# axiom_beta_interface_dummy_v0_13_r1_1_46.net
KiCad netlist of a schematic drawn in EAGLE
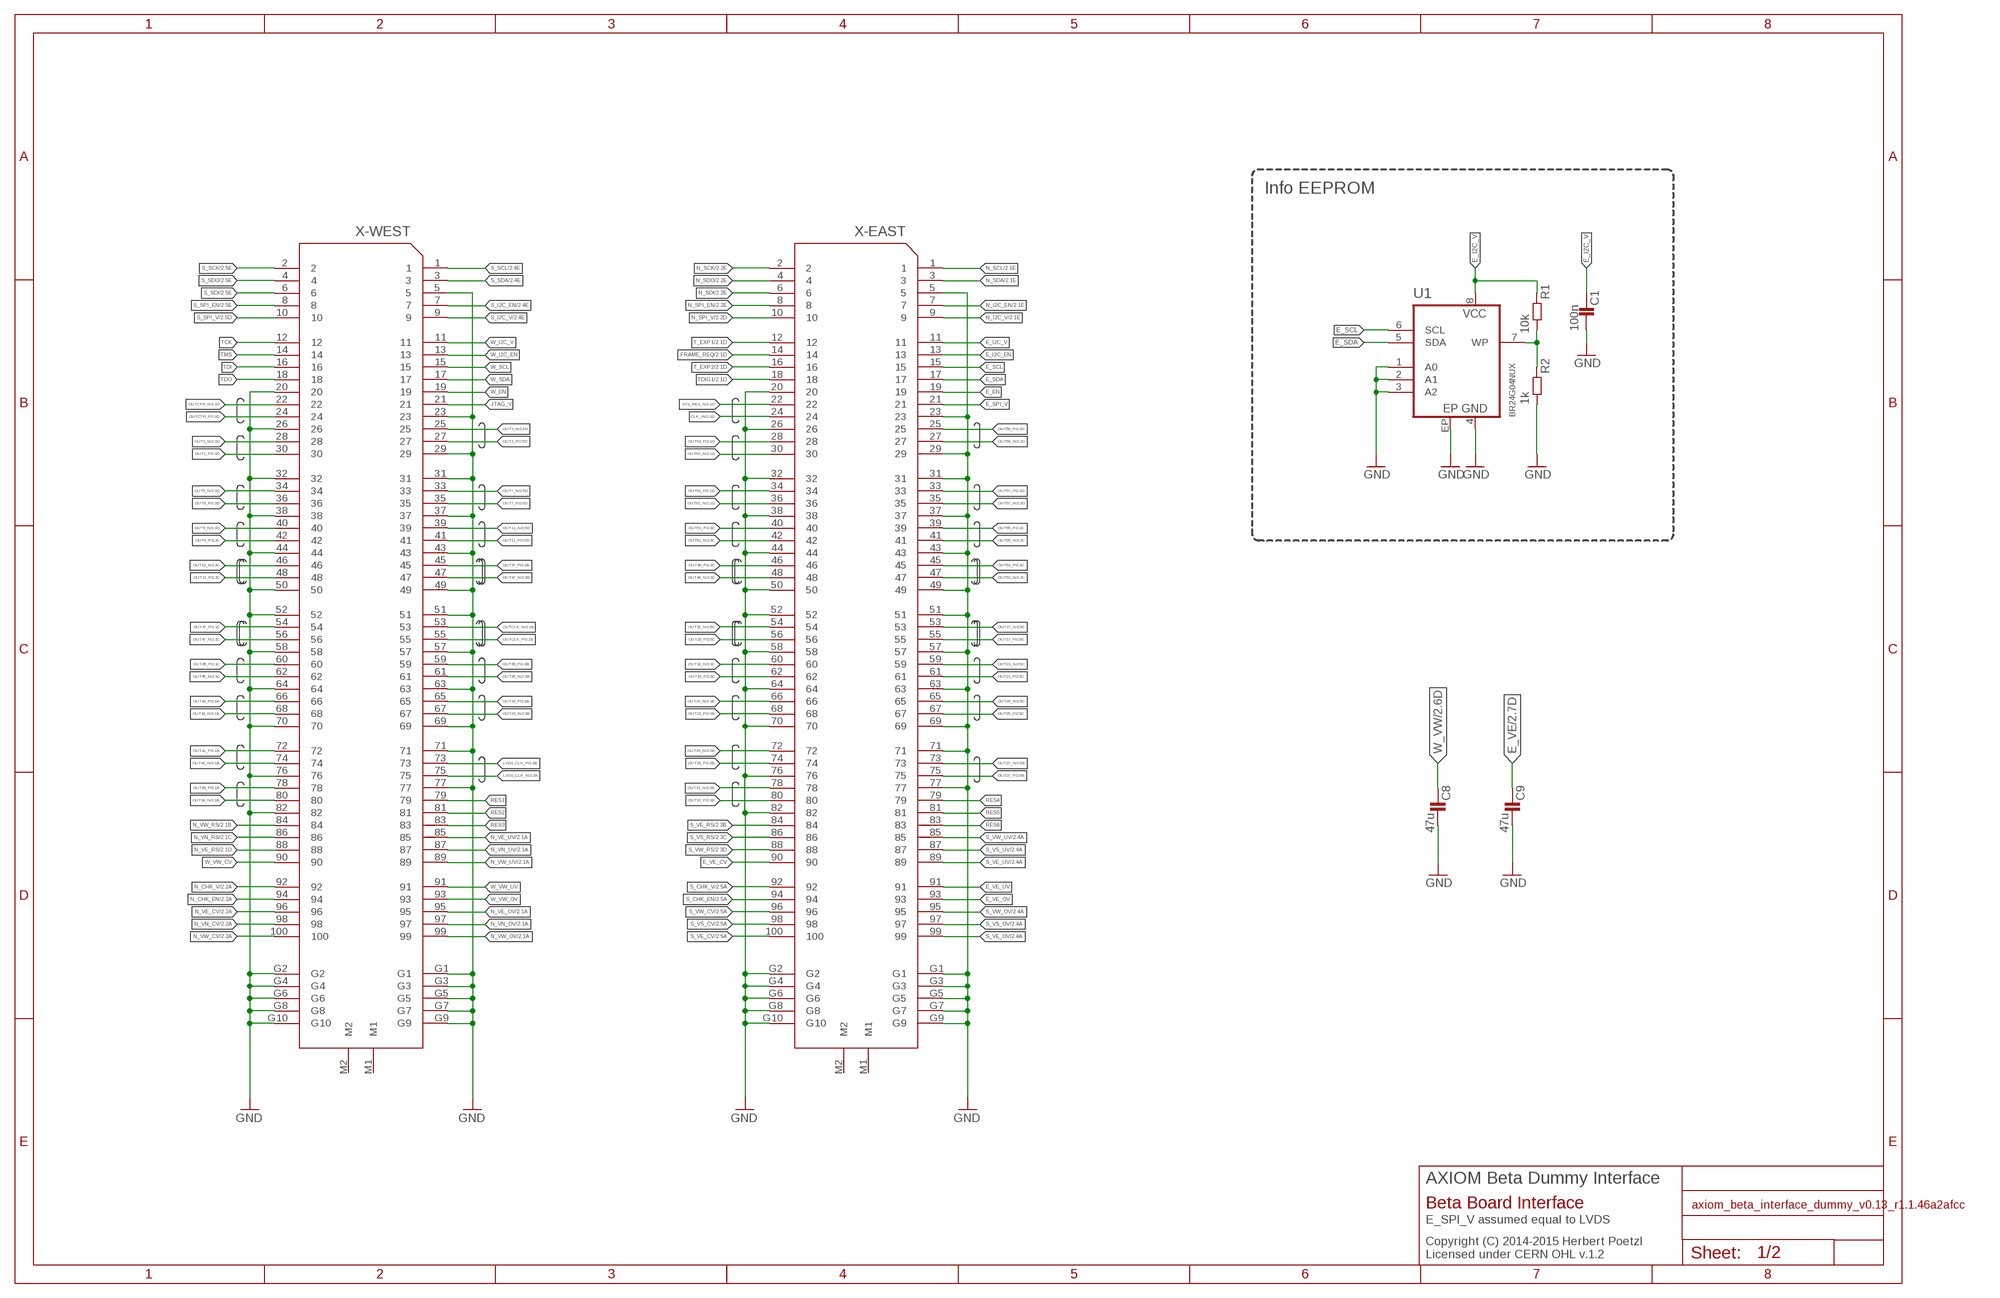
[diagram p0: schematic, sheet 1]
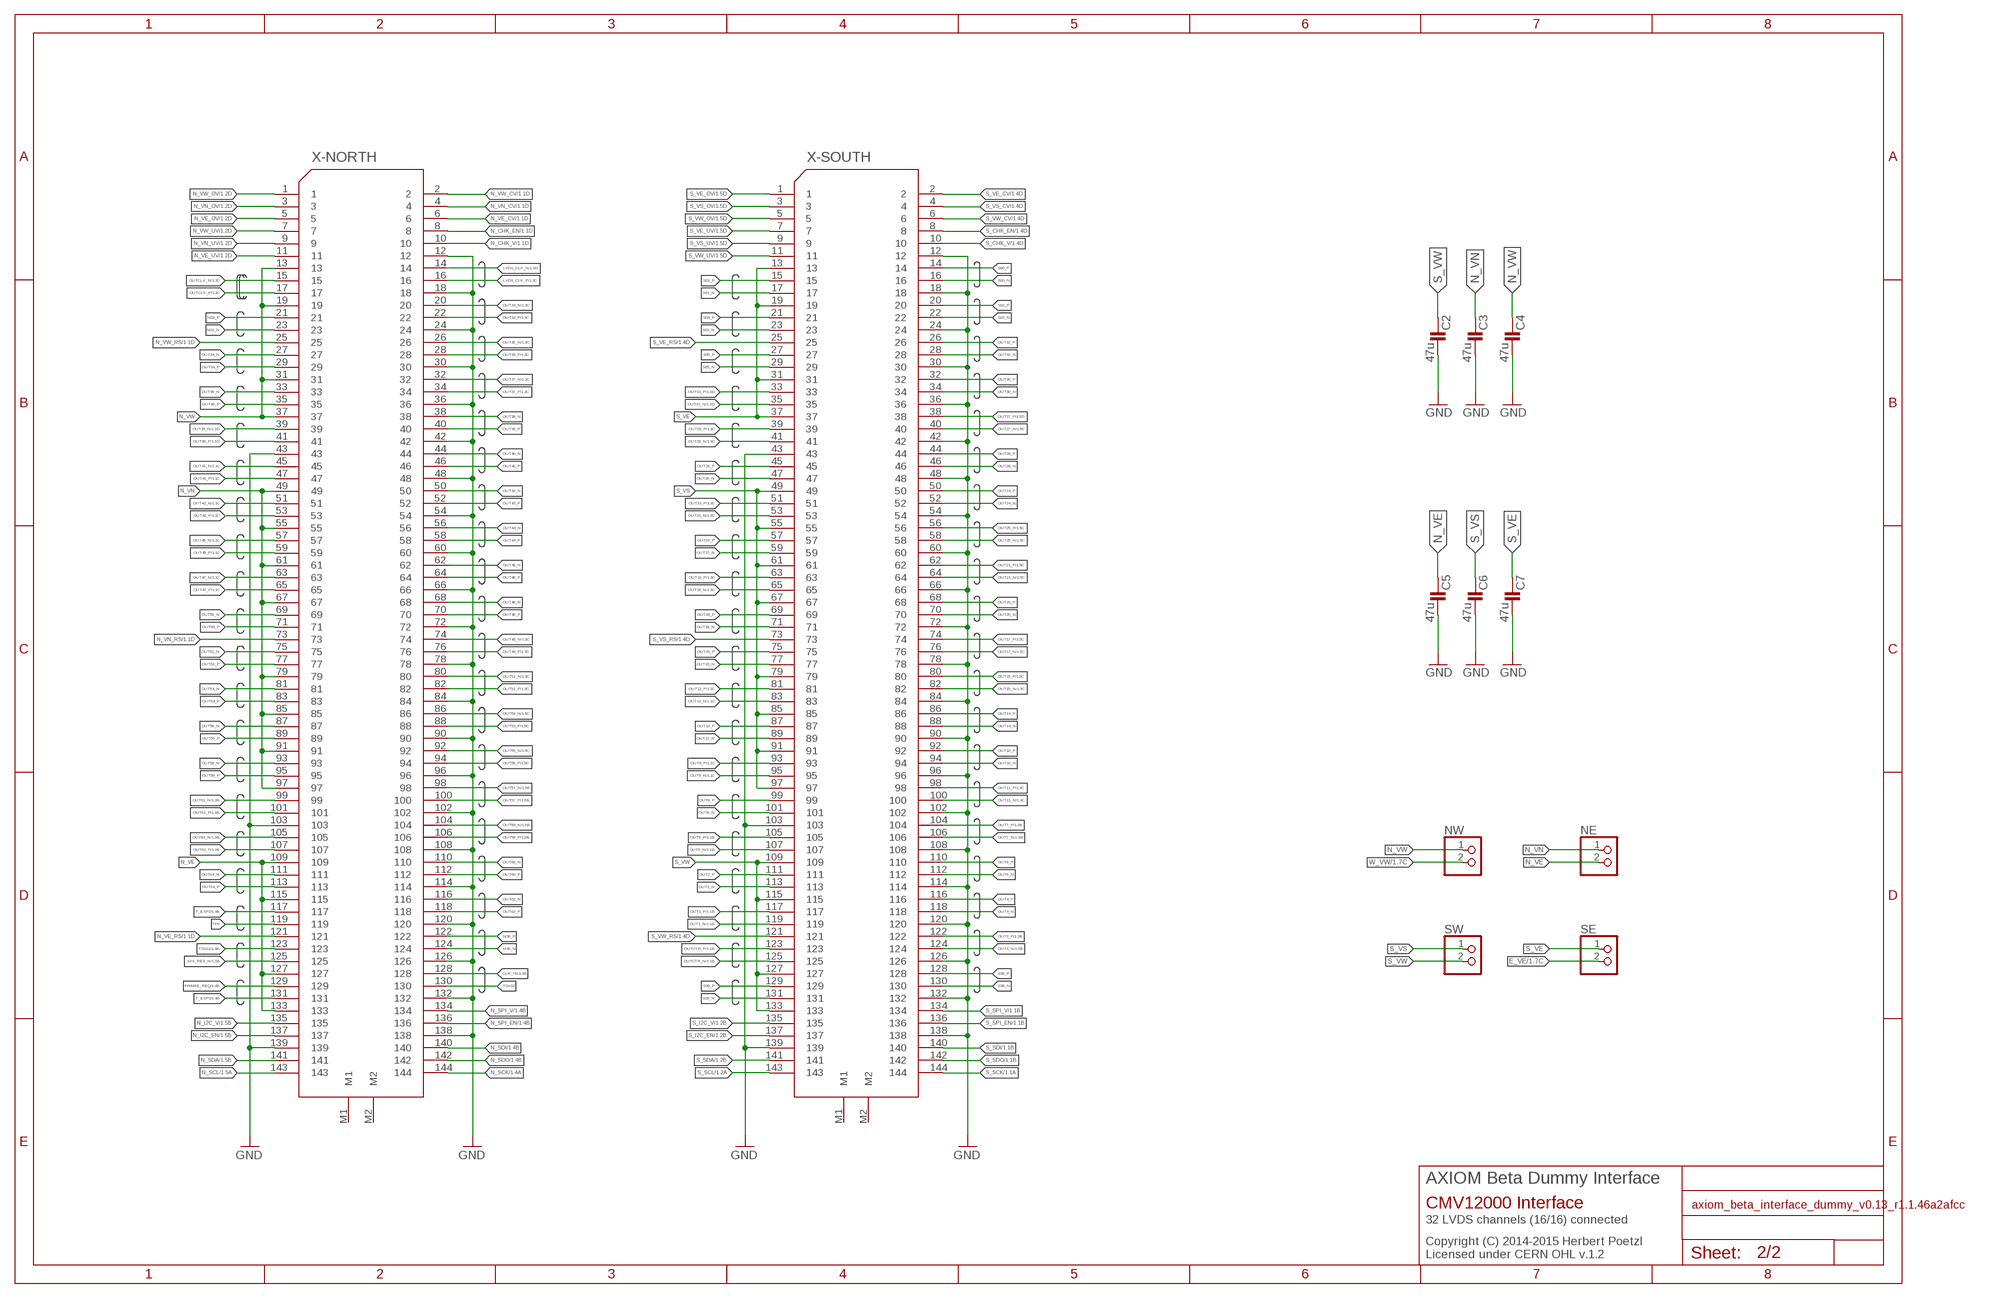
[diagram p1: schematic, sheet 2]

(export (version "E")
  (design (tool "Eeschema 10.0.6"))
  (components
    (comp (ref "C2")
      (value "47u")
      (footprint "eagle-import:0805-B")
      (libsource (lib "eagle-import") (part "C0805-B"))
    )
    (comp (ref "C3")
      (value "47u")
      (footprint "eagle-import:0805-B")
      (libsource (lib "eagle-import") (part "C0805-B"))
    )
    (comp (ref "C4")
      (value "47u")
      (footprint "eagle-import:0805-B")
      (libsource (lib "eagle-import") (part "C0805-B"))
    )
    (comp (ref "C5")
      (value "47u")
      (footprint "eagle-import:0805-B")
      (libsource (lib "eagle-import") (part "C0805-B"))
    )
    (comp (ref "C6")
      (value "47u")
      (footprint "eagle-import:0805-B")
      (libsource (lib "eagle-import") (part "C0805-B"))
    )
    (comp (ref "C7")
      (value "47u")
      (footprint "eagle-import:0805-B")
      (libsource (lib "eagle-import") (part "C0805-B"))
    )
    (comp (ref "NE")
      (value "PINHD-1X02_2.54")
      (footprint "eagle-import:1X02")
      (libsource (lib "eagle-import") (part "PINHD-1X02_2.54"))
    )
    (comp (ref "NW")
      (value "PINHD-1X02_2.54")
      (footprint "eagle-import:1X02")
      (libsource (lib "eagle-import") (part "PINHD-1X02_2.54"))
    )
    (comp (ref "SE")
      (value "PINHD-1X02_2.54")
      (footprint "eagle-import:1X02")
      (libsource (lib "eagle-import") (part "PINHD-1X02_2.54"))
    )
    (comp (ref "SW")
      (value "PINHD-1X02_2.54")
      (footprint "eagle-import:1X02")
      (libsource (lib "eagle-import") (part "PINHD-1X02_2.54"))
    )
    (comp (ref "X-NORTH")
      (value "FX10-144S")
      (footprint "eagle-import:FX10A-144S")
      (libsource (lib "eagle-import") (part "FX10-144S"))
    )
    (comp (ref "X-SOUTH")
      (value "FX10-144S")
      (footprint "eagle-import:FX10A-144S")
      (libsource (lib "eagle-import") (part "FX10-144S"))
    )
    (comp (ref "C1")
      (value "100n")
      (footprint "eagle-import:0402-B")
      (libsource (lib "eagle-import") (part "C0402-B"))
    )
    (comp (ref "C8")
      (value "47u")
      (footprint "eagle-import:0805-B")
      (libsource (lib "eagle-import") (part "C0805-B"))
    )
    (comp (ref "C9")
      (value "47u")
      (footprint "eagle-import:0805-B")
      (libsource (lib "eagle-import") (part "C0805-B"))
    )
    (comp (ref "R1")
      (value "10k")
      (footprint "eagle-import:0402-B")
      (libsource (lib "eagle-import") (part "R0402-B"))
    )
    (comp (ref "R2")
      (value "1k")
      (footprint "eagle-import:0402-B")
      (libsource (lib "eagle-import") (part "R0402-B"))
    )
    (comp (ref "U1")
      (value "BR24G04NUX")
      (footprint "eagle-import:DFN200X300X100-9N")
      (libsource (lib "eagle-import") (part "BR24G04NUX"))
    )
    (comp (ref "X-EAST")
      (value "FX10-100/10P")
      (footprint "eagle-import:FX10A-100P_10")
      (libsource (lib "eagle-import") (part "FX10-100/10P"))
    )
    (comp (ref "X-WEST")
      (value "FX10-100/10P")
      (footprint "eagle-import:FX10A-100P_10")
      (libsource (lib "eagle-import") (part "FX10-100/10P"))
    )
  )
  (nets
    (net (code "1") (name "CLK_IN") (class "Default")
      (node (ref "X-EAST") (pin "24") (pinfunction "24_24") (pintype "bidirectional"))
      (node (ref "X-NORTH") (pin "128") (pinfunction "128_128") (pintype "bidirectional"))
    )
    (net (code "2") (name "E_EN") (class "Default")
      (node (ref "X-EAST") (pin "19") (pinfunction "19_19") (pintype "bidirectional"))
    )
    (net (code "3") (name "E_I2C_EN") (class "Default")
      (node (ref "X-EAST") (pin "13") (pinfunction "13_13") (pintype "bidirectional"))
    )
    (net (code "4") (name "E_I2C_V") (class "Default")
      (node (ref "C1") (pin "1") (pinfunction "1_1") (pintype "passive"))
      (node (ref "R1") (pin "1") (pinfunction "1_1") (pintype "passive"))
      (node (ref "U1") (pin "8") (pinfunction "VCC_8") (pintype "power_in"))
      (node (ref "X-EAST") (pin "11") (pinfunction "11_11") (pintype "bidirectional"))
    )
    (net (code "5") (name "E_SCL") (class "Default")
      (node (ref "U1") (pin "6") (pinfunction "SCL_6") (pintype "input"))
      (node (ref "X-EAST") (pin "15") (pinfunction "15_15") (pintype "bidirectional"))
    )
    (net (code "6") (name "E_SDA") (class "Default")
      (node (ref "U1") (pin "5") (pinfunction "SDA_5") (pintype "bidirectional"))
      (node (ref "X-EAST") (pin "17") (pinfunction "17_17") (pintype "bidirectional"))
    )
    (net (code "7") (name "E_SPI_V") (class "Default")
      (node (ref "X-EAST") (pin "21") (pinfunction "21_21") (pintype "bidirectional"))
    )
    (net (code "8") (name "E_VE") (class "Default")
      (node (ref "C9") (pin "1") (pinfunction "1_1") (pintype "passive"))
      (node (ref "SE") (pin "2") (pinfunction "2_2") (pintype "passive"))
    )
    (net (code "9") (name "E_VE_CV") (class "Default")
      (node (ref "X-EAST") (pin "90") (pinfunction "90_90") (pintype "bidirectional"))
    )
    (net (code "10") (name "E_VE_OV") (class "Default")
      (node (ref "X-EAST") (pin "93") (pinfunction "93_93") (pintype "bidirectional"))
    )
    (net (code "11") (name "E_VE_UV") (class "Default")
      (node (ref "X-EAST") (pin "91") (pinfunction "91_91") (pintype "bidirectional"))
    )
    (net (code "12") (name "FRAME_REQ") (class "Default")
      (node (ref "X-EAST") (pin "14") (pinfunction "14_14") (pintype "bidirectional"))
      (node (ref "X-NORTH") (pin "129") (pinfunction "129_129") (pintype "bidirectional"))
    )
    (net (code "13") (name "GND") (class "Default")
      (node (ref "C1") (pin "2") (pinfunction "2_2") (pintype "passive"))
      (node (ref "C2") (pin "2") (pinfunction "2_2") (pintype "passive"))
      (node (ref "C3") (pin "2") (pinfunction "2_2") (pintype "passive"))
      (node (ref "C4") (pin "2") (pinfunction "2_2") (pintype "passive"))
      (node (ref "C5") (pin "2") (pinfunction "2_2") (pintype "passive"))
      (node (ref "C6") (pin "2") (pinfunction "2_2") (pintype "passive"))
      (node (ref "C7") (pin "2") (pinfunction "2_2") (pintype "passive"))
      (node (ref "C8") (pin "2") (pinfunction "2_2") (pintype "passive"))
      (node (ref "C9") (pin "2") (pinfunction "2_2") (pintype "passive"))
      (node (ref "R2") (pin "2") (pinfunction "2_2") (pintype "passive"))
      (node (ref "U1") (pin "1") (pinfunction "A0_1") (pintype "input"))
      (node (ref "U1") (pin "2") (pinfunction "A1_2") (pintype "input"))
      (node (ref "U1") (pin "3") (pinfunction "A2_3") (pintype "input"))
      (node (ref "U1") (pin "4") (pinfunction "GND_4") (pintype "passive"))
      (node (ref "U1") (pin "EP") (pinfunction "EP_EP") (pintype "passive"))
      (node (ref "X-EAST") (pin "20") (pinfunction "20_20") (pintype "bidirectional"))
      (node (ref "X-EAST") (pin "23") (pinfunction "23_23") (pintype "bidirectional"))
      (node (ref "X-EAST") (pin "26") (pinfunction "26_26") (pintype "bidirectional"))
      (node (ref "X-EAST") (pin "29") (pinfunction "29_29") (pintype "bidirectional"))
      (node (ref "X-EAST") (pin "31") (pinfunction "31_31") (pintype "bidirectional"))
      (node (ref "X-EAST") (pin "32") (pinfunction "32_32") (pintype "bidirectional"))
      (node (ref "X-EAST") (pin "37") (pinfunction "37_37") (pintype "bidirectional"))
      (node (ref "X-EAST") (pin "38") (pinfunction "38_38") (pintype "bidirectional"))
      (node (ref "X-EAST") (pin "43") (pinfunction "43_43") (pintype "bidirectional"))
      (node (ref "X-EAST") (pin "44") (pinfunction "44_44") (pintype "bidirectional"))
      (node (ref "X-EAST") (pin "49") (pinfunction "49_49") (pintype "bidirectional"))
      (node (ref "X-EAST") (pin "5") (pinfunction "5_5") (pintype "bidirectional"))
      (node (ref "X-EAST") (pin "50") (pinfunction "50_50") (pintype "bidirectional"))
      (node (ref "X-EAST") (pin "51") (pinfunction "51_51") (pintype "bidirectional"))
      (node (ref "X-EAST") (pin "52") (pinfunction "52_52") (pintype "bidirectional"))
      (node (ref "X-EAST") (pin "57") (pinfunction "57_57") (pintype "bidirectional"))
      (node (ref "X-EAST") (pin "58") (pinfunction "58_58") (pintype "bidirectional"))
      (node (ref "X-EAST") (pin "63") (pinfunction "63_63") (pintype "bidirectional"))
      (node (ref "X-EAST") (pin "64") (pinfunction "64_64") (pintype "bidirectional"))
      (node (ref "X-EAST") (pin "69") (pinfunction "69_69") (pintype "bidirectional"))
      (node (ref "X-EAST") (pin "70") (pinfunction "70_70") (pintype "bidirectional"))
      (node (ref "X-EAST") (pin "71") (pinfunction "71_71") (pintype "bidirectional"))
      (node (ref "X-EAST") (pin "76") (pinfunction "76_76") (pintype "bidirectional"))
      (node (ref "X-EAST") (pin "77") (pinfunction "77_77") (pintype "bidirectional"))
      (node (ref "X-EAST") (pin "82") (pinfunction "82_82") (pintype "bidirectional"))
      (node (ref "X-EAST") (pin "G1") (pinfunction "G1_G1") (pintype "bidirectional"))
      (node (ref "X-EAST") (pin "G10") (pinfunction "G10_G10") (pintype "bidirectional"))
      (node (ref "X-EAST") (pin "G2") (pinfunction "G2_G2") (pintype "bidirectional"))
      (node (ref "X-EAST") (pin "G3") (pinfunction "G3_G3") (pintype "bidirectional"))
      (node (ref "X-EAST") (pin "G4") (pinfunction "G4_G4") (pintype "bidirectional"))
      (node (ref "X-EAST") (pin "G5") (pinfunction "G5_G5") (pintype "bidirectional"))
      (node (ref "X-EAST") (pin "G6") (pinfunction "G6_G6") (pintype "bidirectional"))
      (node (ref "X-EAST") (pin "G7") (pinfunction "G7_G7") (pintype "bidirectional"))
      (node (ref "X-EAST") (pin "G8") (pinfunction "G8_G8") (pintype "bidirectional"))
      (node (ref "X-EAST") (pin "G9") (pinfunction "G9_G9") (pintype "bidirectional"))
      (node (ref "X-NORTH") (pin "102") (pinfunction "102_102") (pintype "bidirectional"))
      (node (ref "X-NORTH") (pin "103") (pinfunction "103_103") (pintype "bidirectional"))
      (node (ref "X-NORTH") (pin "108") (pinfunction "108_108") (pintype "bidirectional"))
      (node (ref "X-NORTH") (pin "114") (pinfunction "114_114") (pintype "bidirectional"))
      (node (ref "X-NORTH") (pin "12") (pinfunction "12_12") (pintype "bidirectional"))
      (node (ref "X-NORTH") (pin "120") (pinfunction "120_120") (pintype "bidirectional"))
      (node (ref "X-NORTH") (pin "126") (pinfunction "126_126") (pintype "bidirectional"))
      (node (ref "X-NORTH") (pin "132") (pinfunction "132_132") (pintype "bidirectional"))
      (node (ref "X-NORTH") (pin "138") (pinfunction "138_138") (pintype "bidirectional"))
      (node (ref "X-NORTH") (pin "139") (pinfunction "139_139") (pintype "bidirectional"))
      (node (ref "X-NORTH") (pin "18") (pinfunction "18_18") (pintype "bidirectional"))
      (node (ref "X-NORTH") (pin "24") (pinfunction "24_24") (pintype "bidirectional"))
      (node (ref "X-NORTH") (pin "30") (pinfunction "30_30") (pintype "bidirectional"))
      (node (ref "X-NORTH") (pin "36") (pinfunction "36_36") (pintype "bidirectional"))
      (node (ref "X-NORTH") (pin "42") (pinfunction "42_42") (pintype "bidirectional"))
      (node (ref "X-NORTH") (pin "43") (pinfunction "43_43") (pintype "bidirectional"))
      (node (ref "X-NORTH") (pin "48") (pinfunction "48_48") (pintype "bidirectional"))
      (node (ref "X-NORTH") (pin "54") (pinfunction "54_54") (pintype "bidirectional"))
      (node (ref "X-NORTH") (pin "60") (pinfunction "60_60") (pintype "bidirectional"))
      (node (ref "X-NORTH") (pin "66") (pinfunction "66_66") (pintype "bidirectional"))
      (node (ref "X-NORTH") (pin "72") (pinfunction "72_72") (pintype "bidirectional"))
      (node (ref "X-NORTH") (pin "78") (pinfunction "78_78") (pintype "bidirectional"))
      (node (ref "X-NORTH") (pin "84") (pinfunction "84_84") (pintype "bidirectional"))
      (node (ref "X-NORTH") (pin "90") (pinfunction "90_90") (pintype "bidirectional"))
      (node (ref "X-NORTH") (pin "96") (pinfunction "96_96") (pintype "bidirectional"))
      (node (ref "X-SOUTH") (pin "102") (pinfunction "102_102") (pintype "bidirectional"))
      (node (ref "X-SOUTH") (pin "103") (pinfunction "103_103") (pintype "bidirectional"))
      (node (ref "X-SOUTH") (pin "108") (pinfunction "108_108") (pintype "bidirectional"))
      (node (ref "X-SOUTH") (pin "114") (pinfunction "114_114") (pintype "bidirectional"))
      (node (ref "X-SOUTH") (pin "12") (pinfunction "12_12") (pintype "bidirectional"))
      (node (ref "X-SOUTH") (pin "120") (pinfunction "120_120") (pintype "bidirectional"))
      (node (ref "X-SOUTH") (pin "126") (pinfunction "126_126") (pintype "bidirectional"))
      (node (ref "X-SOUTH") (pin "132") (pinfunction "132_132") (pintype "bidirectional"))
      (node (ref "X-SOUTH") (pin "138") (pinfunction "138_138") (pintype "bidirectional"))
      (node (ref "X-SOUTH") (pin "139") (pinfunction "139_139") (pintype "bidirectional"))
      (node (ref "X-SOUTH") (pin "18") (pinfunction "18_18") (pintype "bidirectional"))
      (node (ref "X-SOUTH") (pin "24") (pinfunction "24_24") (pintype "bidirectional"))
      (node (ref "X-SOUTH") (pin "30") (pinfunction "30_30") (pintype "bidirectional"))
      (node (ref "X-SOUTH") (pin "36") (pinfunction "36_36") (pintype "bidirectional"))
      (node (ref "X-SOUTH") (pin "42") (pinfunction "42_42") (pintype "bidirectional"))
      (node (ref "X-SOUTH") (pin "43") (pinfunction "43_43") (pintype "bidirectional"))
      (node (ref "X-SOUTH") (pin "48") (pinfunction "48_48") (pintype "bidirectional"))
      (node (ref "X-SOUTH") (pin "54") (pinfunction "54_54") (pintype "bidirectional"))
      (node (ref "X-SOUTH") (pin "60") (pinfunction "60_60") (pintype "bidirectional"))
      (node (ref "X-SOUTH") (pin "66") (pinfunction "66_66") (pintype "bidirectional"))
      (node (ref "X-SOUTH") (pin "72") (pinfunction "72_72") (pintype "bidirectional"))
      (node (ref "X-SOUTH") (pin "78") (pinfunction "78_78") (pintype "bidirectional"))
      (node (ref "X-SOUTH") (pin "84") (pinfunction "84_84") (pintype "bidirectional"))
      (node (ref "X-SOUTH") (pin "90") (pinfunction "90_90") (pintype "bidirectional"))
      (node (ref "X-SOUTH") (pin "96") (pinfunction "96_96") (pintype "bidirectional"))
      (node (ref "X-WEST") (pin "20") (pinfunction "20_20") (pintype "bidirectional"))
      (node (ref "X-WEST") (pin "23") (pinfunction "23_23") (pintype "bidirectional"))
      (node (ref "X-WEST") (pin "26") (pinfunction "26_26") (pintype "bidirectional"))
      (node (ref "X-WEST") (pin "29") (pinfunction "29_29") (pintype "bidirectional"))
      (node (ref "X-WEST") (pin "31") (pinfunction "31_31") (pintype "bidirectional"))
      (node (ref "X-WEST") (pin "32") (pinfunction "32_32") (pintype "bidirectional"))
      (node (ref "X-WEST") (pin "37") (pinfunction "37_37") (pintype "bidirectional"))
      (node (ref "X-WEST") (pin "38") (pinfunction "38_38") (pintype "bidirectional"))
      (node (ref "X-WEST") (pin "43") (pinfunction "43_43") (pintype "bidirectional"))
      (node (ref "X-WEST") (pin "44") (pinfunction "44_44") (pintype "bidirectional"))
      (node (ref "X-WEST") (pin "49") (pinfunction "49_49") (pintype "bidirectional"))
      (node (ref "X-WEST") (pin "5") (pinfunction "5_5") (pintype "bidirectional"))
      (node (ref "X-WEST") (pin "50") (pinfunction "50_50") (pintype "bidirectional"))
      (node (ref "X-WEST") (pin "51") (pinfunction "51_51") (pintype "bidirectional"))
      (node (ref "X-WEST") (pin "52") (pinfunction "52_52") (pintype "bidirectional"))
      (node (ref "X-WEST") (pin "57") (pinfunction "57_57") (pintype "bidirectional"))
      (node (ref "X-WEST") (pin "58") (pinfunction "58_58") (pintype "bidirectional"))
      (node (ref "X-WEST") (pin "63") (pinfunction "63_63") (pintype "bidirectional"))
      (node (ref "X-WEST") (pin "64") (pinfunction "64_64") (pintype "bidirectional"))
      (node (ref "X-WEST") (pin "69") (pinfunction "69_69") (pintype "bidirectional"))
      (node (ref "X-WEST") (pin "70") (pinfunction "70_70") (pintype "bidirectional"))
      (node (ref "X-WEST") (pin "71") (pinfunction "71_71") (pintype "bidirectional"))
      (node (ref "X-WEST") (pin "76") (pinfunction "76_76") (pintype "bidirectional"))
      (node (ref "X-WEST") (pin "77") (pinfunction "77_77") (pintype "bidirectional"))
      (node (ref "X-WEST") (pin "82") (pinfunction "82_82") (pintype "bidirectional"))
      (node (ref "X-WEST") (pin "G1") (pinfunction "G1_G1") (pintype "bidirectional"))
      (node (ref "X-WEST") (pin "G10") (pinfunction "G10_G10") (pintype "bidirectional"))
      (node (ref "X-WEST") (pin "G2") (pinfunction "G2_G2") (pintype "bidirectional"))
      (node (ref "X-WEST") (pin "G3") (pinfunction "G3_G3") (pintype "bidirectional"))
      (node (ref "X-WEST") (pin "G4") (pinfunction "G4_G4") (pintype "bidirectional"))
      (node (ref "X-WEST") (pin "G5") (pinfunction "G5_G5") (pintype "bidirectional"))
      (node (ref "X-WEST") (pin "G6") (pinfunction "G6_G6") (pintype "bidirectional"))
      (node (ref "X-WEST") (pin "G7") (pinfunction "G7_G7") (pintype "bidirectional"))
      (node (ref "X-WEST") (pin "G8") (pinfunction "G8_G8") (pintype "bidirectional"))
      (node (ref "X-WEST") (pin "G9") (pinfunction "G9_G9") (pintype "bidirectional"))
    )
    (net (code "14") (name "JTAG_V") (class "Default")
      (node (ref "X-WEST") (pin "21") (pinfunction "21_21") (pintype "bidirectional"))
    )
    (net (code "15") (name "LVDS_CLK_N") (class "Default")
      (node (ref "X-NORTH") (pin "14") (pinfunction "14_14") (pintype "bidirectional"))
      (node (ref "X-WEST") (pin "75") (pinfunction "75_75") (pintype "bidirectional"))
    )
    (net (code "16") (name "LVDS_CLK_P") (class "Default")
      (node (ref "X-NORTH") (pin "16") (pinfunction "16_16") (pintype "bidirectional"))
      (node (ref "X-WEST") (pin "73") (pinfunction "73_73") (pintype "bidirectional"))
    )
    (net (code "17") (name "N03_N") (class "Default")
      (node (ref "X-NORTH") (pin "23") (pinfunction "23_23") (pintype "bidirectional"))
    )
    (net (code "18") (name "N03_P") (class "Default")
      (node (ref "X-NORTH") (pin "21") (pinfunction "21_21") (pintype "bidirectional"))
    )
    (net (code "19") (name "N36_N") (class "Default")
      (node (ref "X-NORTH") (pin "124") (pinfunction "124_124") (pintype "bidirectional"))
    )
    (net (code "20") (name "N36_P") (class "Default")
      (node (ref "X-NORTH") (pin "122") (pinfunction "122_122") (pintype "bidirectional"))
    )
    (net (code "21") (name "N_CHK_EN") (class "Default")
      (node (ref "X-NORTH") (pin "8") (pinfunction "8_8") (pintype "bidirectional"))
      (node (ref "X-WEST") (pin "94") (pinfunction "94_94") (pintype "bidirectional"))
    )
    (net (code "22") (name "N_CHK_V") (class "Default")
      (node (ref "X-NORTH") (pin "10") (pinfunction "10_10") (pintype "bidirectional"))
      (node (ref "X-WEST") (pin "92") (pinfunction "92_92") (pintype "bidirectional"))
    )
    (net (code "23") (name "N_I2C_EN") (class "Default")
      (node (ref "X-EAST") (pin "7") (pinfunction "7_7") (pintype "bidirectional"))
      (node (ref "X-NORTH") (pin "137") (pinfunction "137_137") (pintype "bidirectional"))
    )
    (net (code "24") (name "N_I2C_V") (class "Default")
      (node (ref "X-EAST") (pin "9") (pinfunction "9_9") (pintype "bidirectional"))
      (node (ref "X-NORTH") (pin "135") (pinfunction "135_135") (pintype "bidirectional"))
    )
    (net (code "25") (name "N_SCK") (class "Default")
      (node (ref "X-EAST") (pin "2") (pinfunction "2_2") (pintype "bidirectional"))
      (node (ref "X-NORTH") (pin "144") (pinfunction "144_144") (pintype "bidirectional"))
    )
    (net (code "26") (name "N_SCL") (class "Default")
      (node (ref "X-EAST") (pin "1") (pinfunction "1_1") (pintype "bidirectional"))
      (node (ref "X-NORTH") (pin "143") (pinfunction "143_143") (pintype "bidirectional"))
    )
    (net (code "27") (name "N_SDA") (class "Default")
      (node (ref "X-EAST") (pin "3") (pinfunction "3_3") (pintype "bidirectional"))
      (node (ref "X-NORTH") (pin "141") (pinfunction "141_141") (pintype "bidirectional"))
    )
    (net (code "28") (name "N_SDI") (class "Default")
      (node (ref "X-EAST") (pin "6") (pinfunction "6_6") (pintype "bidirectional"))
      (node (ref "X-NORTH") (pin "140") (pinfunction "140_140") (pintype "bidirectional"))
    )
    (net (code "29") (name "N_SDO") (class "Default")
      (node (ref "X-EAST") (pin "4") (pinfunction "4_4") (pintype "bidirectional"))
      (node (ref "X-NORTH") (pin "142") (pinfunction "142_142") (pintype "bidirectional"))
    )
    (net (code "30") (name "N_SPI_EN") (class "Default")
      (node (ref "X-EAST") (pin "8") (pinfunction "8_8") (pintype "bidirectional"))
      (node (ref "X-NORTH") (pin "136") (pinfunction "136_136") (pintype "bidirectional"))
    )
    (net (code "31") (name "N_SPI_V") (class "Default")
      (node (ref "X-EAST") (pin "10") (pinfunction "10_10") (pintype "bidirectional"))
      (node (ref "X-NORTH") (pin "134") (pinfunction "134_134") (pintype "bidirectional"))
    )
    (net (code "32") (name "N_VE") (class "Default")
      (node (ref "C5") (pin "1") (pinfunction "1_1") (pintype "passive"))
      (node (ref "NE") (pin "2") (pinfunction "2_2") (pintype "passive"))
      (node (ref "X-NORTH") (pin "109") (pinfunction "109_109") (pintype "bidirectional"))
      (node (ref "X-NORTH") (pin "115") (pinfunction "115_115") (pintype "bidirectional"))
      (node (ref "X-NORTH") (pin "127") (pinfunction "127_127") (pintype "bidirectional"))
      (node (ref "X-NORTH") (pin "133") (pinfunction "133_133") (pintype "bidirectional"))
    )
    (net (code "33") (name "N_VE_CV") (class "Default")
      (node (ref "X-NORTH") (pin "6") (pinfunction "6_6") (pintype "bidirectional"))
      (node (ref "X-WEST") (pin "96") (pinfunction "96_96") (pintype "bidirectional"))
    )
    (net (code "34") (name "N_VE_OV") (class "Default")
      (node (ref "X-NORTH") (pin "5") (pinfunction "5_5") (pintype "bidirectional"))
      (node (ref "X-WEST") (pin "95") (pinfunction "95_95") (pintype "bidirectional"))
    )
    (net (code "35") (name "N_VE_RS") (class "Default")
      (node (ref "X-NORTH") (pin "121") (pinfunction "121_121") (pintype "bidirectional"))
      (node (ref "X-WEST") (pin "88") (pinfunction "88_88") (pintype "bidirectional"))
    )
    (net (code "36") (name "N_VE_UV") (class "Default")
      (node (ref "X-NORTH") (pin "11") (pinfunction "11_11") (pintype "bidirectional"))
      (node (ref "X-WEST") (pin "85") (pinfunction "85_85") (pintype "bidirectional"))
    )
    (net (code "37") (name "N_VN") (class "Default")
      (node (ref "C3") (pin "1") (pinfunction "1_1") (pintype "passive"))
      (node (ref "NE") (pin "1") (pinfunction "1_1") (pintype "passive"))
      (node (ref "X-NORTH") (pin "49") (pinfunction "49_49") (pintype "bidirectional"))
      (node (ref "X-NORTH") (pin "55") (pinfunction "55_55") (pintype "bidirectional"))
      (node (ref "X-NORTH") (pin "61") (pinfunction "61_61") (pintype "bidirectional"))
      (node (ref "X-NORTH") (pin "67") (pinfunction "67_67") (pintype "bidirectional"))
      (node (ref "X-NORTH") (pin "79") (pinfunction "79_79") (pintype "bidirectional"))
      (node (ref "X-NORTH") (pin "85") (pinfunction "85_85") (pintype "bidirectional"))
      (node (ref "X-NORTH") (pin "91") (pinfunction "91_91") (pintype "bidirectional"))
      (node (ref "X-NORTH") (pin "97") (pinfunction "97_97") (pintype "bidirectional"))
    )
    (net (code "38") (name "N_VN_CV") (class "Default")
      (node (ref "X-NORTH") (pin "4") (pinfunction "4_4") (pintype "bidirectional"))
      (node (ref "X-WEST") (pin "98") (pinfunction "98_98") (pintype "bidirectional"))
    )
    (net (code "39") (name "N_VN_OV") (class "Default")
      (node (ref "X-NORTH") (pin "3") (pinfunction "3_3") (pintype "bidirectional"))
      (node (ref "X-WEST") (pin "97") (pinfunction "97_97") (pintype "bidirectional"))
    )
    (net (code "40") (name "N_VN_RS") (class "Default")
      (node (ref "X-NORTH") (pin "73") (pinfunction "73_73") (pintype "bidirectional"))
      (node (ref "X-WEST") (pin "86") (pinfunction "86_86") (pintype "bidirectional"))
    )
    (net (code "41") (name "N_VN_UV") (class "Default")
      (node (ref "X-NORTH") (pin "9") (pinfunction "9_9") (pintype "bidirectional"))
      (node (ref "X-WEST") (pin "87") (pinfunction "87_87") (pintype "bidirectional"))
    )
    (net (code "42") (name "N_VW") (class "Default")
      (node (ref "C4") (pin "1") (pinfunction "1_1") (pintype "passive"))
      (node (ref "NW") (pin "1") (pinfunction "1_1") (pintype "passive"))
      (node (ref "X-NORTH") (pin "13") (pinfunction "13_13") (pintype "bidirectional"))
      (node (ref "X-NORTH") (pin "19") (pinfunction "19_19") (pintype "bidirectional"))
      (node (ref "X-NORTH") (pin "31") (pinfunction "31_31") (pintype "bidirectional"))
      (node (ref "X-NORTH") (pin "37") (pinfunction "37_37") (pintype "bidirectional"))
    )
    (net (code "43") (name "N_VW_CV") (class "Default")
      (node (ref "X-NORTH") (pin "2") (pinfunction "2_2") (pintype "bidirectional"))
      (node (ref "X-WEST") (pin "100") (pinfunction "100_100") (pintype "bidirectional"))
    )
    (net (code "44") (name "N_VW_OV") (class "Default")
      (node (ref "X-NORTH") (pin "1") (pinfunction "1_1") (pintype "bidirectional"))
      (node (ref "X-WEST") (pin "99") (pinfunction "99_99") (pintype "bidirectional"))
    )
    (net (code "45") (name "N_VW_RS") (class "Default")
      (node (ref "X-NORTH") (pin "25") (pinfunction "25_25") (pintype "bidirectional"))
      (node (ref "X-WEST") (pin "84") (pinfunction "84_84") (pintype "bidirectional"))
    )
    (net (code "46") (name "N_VW_UV") (class "Default")
      (node (ref "X-NORTH") (pin "7") (pinfunction "7_7") (pintype "bidirectional"))
      (node (ref "X-WEST") (pin "89") (pinfunction "89_89") (pintype "bidirectional"))
    )
    (net (code "47") (name "Net-(U1-WP)") (class "Default")
      (node (ref "R1") (pin "2") (pinfunction "2_2") (pintype "passive"))
      (node (ref "R2") (pin "1") (pinfunction "1_1") (pintype "passive"))
      (node (ref "U1") (pin "7") (pinfunction "WP_7") (pintype "input"))
    )
    (net (code "48") (name "OUT1_N") (class "Default")
      (node (ref "X-SOUTH") (pin "119") (pinfunction "119_119") (pintype "bidirectional"))
      (node (ref "X-WEST") (pin "28") (pinfunction "28_28") (pintype "bidirectional"))
    )
    (net (code "49") (name "OUT1_P") (class "Default")
      (node (ref "X-SOUTH") (pin "117") (pinfunction "117_117") (pintype "bidirectional"))
      (node (ref "X-WEST") (pin "30") (pinfunction "30_30") (pintype "bidirectional"))
    )
    (net (code "50") (name "OUT2_N") (class "Default")
      (node (ref "X-SOUTH") (pin "113") (pinfunction "113_113") (pintype "bidirectional"))
    )
    (net (code "51") (name "OUT2_P") (class "Default")
      (node (ref "X-SOUTH") (pin "111") (pinfunction "111_111") (pintype "bidirectional"))
    )
    (net (code "52") (name "OUT3_N") (class "Default")
      (node (ref "X-SOUTH") (pin "124") (pinfunction "124_124") (pintype "bidirectional"))
      (node (ref "X-WEST") (pin "25") (pinfunction "25_25") (pintype "bidirectional"))
    )
    (net (code "53") (name "OUT3_P") (class "Default")
      (node (ref "X-SOUTH") (pin "122") (pinfunction "122_122") (pintype "bidirectional"))
      (node (ref "X-WEST") (pin "27") (pinfunction "27_27") (pintype "bidirectional"))
    )
    (net (code "54") (name "OUT4_N") (class "Default")
      (node (ref "X-SOUTH") (pin "118") (pinfunction "118_118") (pintype "bidirectional"))
    )
    (net (code "55") (name "OUT4_P") (class "Default")
      (node (ref "X-SOUTH") (pin "116") (pinfunction "116_116") (pintype "bidirectional"))
    )
    (net (code "56") (name "OUT5_N") (class "Default")
      (node (ref "X-SOUTH") (pin "107") (pinfunction "107_107") (pintype "bidirectional"))
      (node (ref "X-WEST") (pin "34") (pinfunction "34_34") (pintype "bidirectional"))
    )
    (net (code "57") (name "OUT5_P") (class "Default")
      (node (ref "X-SOUTH") (pin "105") (pinfunction "105_105") (pintype "bidirectional"))
      (node (ref "X-WEST") (pin "36") (pinfunction "36_36") (pintype "bidirectional"))
    )
    (net (code "58") (name "OUT6_N") (class "Default")
      (node (ref "X-SOUTH") (pin "112") (pinfunction "112_112") (pintype "bidirectional"))
    )
    (net (code "59") (name "OUT6_P") (class "Default")
      (node (ref "X-SOUTH") (pin "110") (pinfunction "110_110") (pintype "bidirectional"))
    )
    (net (code "60") (name "OUT7_N") (class "Default")
      (node (ref "X-SOUTH") (pin "106") (pinfunction "106_106") (pintype "bidirectional"))
      (node (ref "X-WEST") (pin "33") (pinfunction "33_33") (pintype "bidirectional"))
    )
    (net (code "61") (name "OUT7_P") (class "Default")
      (node (ref "X-SOUTH") (pin "104") (pinfunction "104_104") (pintype "bidirectional"))
      (node (ref "X-WEST") (pin "35") (pinfunction "35_35") (pintype "bidirectional"))
    )
    (net (code "62") (name "OUT8_N") (class "Default")
      (node (ref "X-SOUTH") (pin "101") (pinfunction "101_101") (pintype "bidirectional"))
    )
    (net (code "63") (name "OUT8_P") (class "Default")
      (node (ref "X-SOUTH") (pin "99") (pinfunction "99_99") (pintype "bidirectional"))
    )
    (net (code "64") (name "OUT9_N") (class "Default")
      (node (ref "X-SOUTH") (pin "95") (pinfunction "95_95") (pintype "bidirectional"))
      (node (ref "X-WEST") (pin "40") (pinfunction "40_40") (pintype "bidirectional"))
    )
    (net (code "65") (name "OUT9_P") (class "Default")
      (node (ref "X-SOUTH") (pin "93") (pinfunction "93_93") (pintype "bidirectional"))
      (node (ref "X-WEST") (pin "42") (pinfunction "42_42") (pintype "bidirectional"))
    )
    (net (code "66") (name "OUT10_N") (class "Default")
      (node (ref "X-SOUTH") (pin "94") (pinfunction "94_94") (pintype "bidirectional"))
    )
    (net (code "67") (name "OUT10_P") (class "Default")
      (node (ref "X-SOUTH") (pin "92") (pinfunction "92_92") (pintype "bidirectional"))
    )
    (net (code "68") (name "OUT11_N") (class "Default")
      (node (ref "X-SOUTH") (pin "100") (pinfunction "100_100") (pintype "bidirectional"))
      (node (ref "X-WEST") (pin "39") (pinfunction "39_39") (pintype "bidirectional"))
    )
    (net (code "69") (name "OUT11_P") (class "Default")
      (node (ref "X-SOUTH") (pin "98") (pinfunction "98_98") (pintype "bidirectional"))
      (node (ref "X-WEST") (pin "41") (pinfunction "41_41") (pintype "bidirectional"))
    )
    (net (code "70") (name "OUT12_N") (class "Default")
      (node (ref "X-SOUTH") (pin "89") (pinfunction "89_89") (pintype "bidirectional"))
    )
    (net (code "71") (name "OUT12_P") (class "Default")
      (node (ref "X-SOUTH") (pin "87") (pinfunction "87_87") (pintype "bidirectional"))
    )
    (net (code "72") (name "OUT13_N") (class "Default")
      (node (ref "X-SOUTH") (pin "83") (pinfunction "83_83") (pintype "bidirectional"))
      (node (ref "X-WEST") (pin "46") (pinfunction "46_46") (pintype "bidirectional"))
    )
    (net (code "73") (name "OUT13_P") (class "Default")
      (node (ref "X-SOUTH") (pin "81") (pinfunction "81_81") (pintype "bidirectional"))
      (node (ref "X-WEST") (pin "48") (pinfunction "48_48") (pintype "bidirectional"))
    )
    (net (code "74") (name "OUT14_N") (class "Default")
      (node (ref "X-SOUTH") (pin "88") (pinfunction "88_88") (pintype "bidirectional"))
    )
    (net (code "75") (name "OUT14_P") (class "Default")
      (node (ref "X-SOUTH") (pin "86") (pinfunction "86_86") (pintype "bidirectional"))
    )
    (net (code "76") (name "OUT15_N") (class "Default")
      (node (ref "X-EAST") (pin "54") (pinfunction "54_54") (pintype "bidirectional"))
      (node (ref "X-SOUTH") (pin "82") (pinfunction "82_82") (pintype "bidirectional"))
    )
    (net (code "77") (name "OUT15_P") (class "Default")
      (node (ref "X-EAST") (pin "56") (pinfunction "56_56") (pintype "bidirectional"))
      (node (ref "X-SOUTH") (pin "80") (pinfunction "80_80") (pintype "bidirectional"))
    )
    (net (code "78") (name "OUT16_N") (class "Default")
      (node (ref "X-SOUTH") (pin "77") (pinfunction "77_77") (pintype "bidirectional"))
    )
    (net (code "79") (name "OUT16_P") (class "Default")
      (node (ref "X-SOUTH") (pin "75") (pinfunction "75_75") (pintype "bidirectional"))
    )
    (net (code "80") (name "OUT17_N") (class "Default")
      (node (ref "X-EAST") (pin "53") (pinfunction "53_53") (pintype "bidirectional"))
      (node (ref "X-SOUTH") (pin "76") (pinfunction "76_76") (pintype "bidirectional"))
    )
    (net (code "81") (name "OUT17_P") (class "Default")
      (node (ref "X-EAST") (pin "55") (pinfunction "55_55") (pintype "bidirectional"))
      (node (ref "X-SOUTH") (pin "74") (pinfunction "74_74") (pintype "bidirectional"))
    )
    (net (code "82") (name "OUT18_N") (class "Default")
      (node (ref "X-SOUTH") (pin "71") (pinfunction "71_71") (pintype "bidirectional"))
    )
    (net (code "83") (name "OUT18_P") (class "Default")
      (node (ref "X-SOUTH") (pin "69") (pinfunction "69_69") (pintype "bidirectional"))
    )
    (net (code "84") (name "OUT19_N") (class "Default")
      (node (ref "X-EAST") (pin "60") (pinfunction "60_60") (pintype "bidirectional"))
      (node (ref "X-SOUTH") (pin "65") (pinfunction "65_65") (pintype "bidirectional"))
    )
    (net (code "85") (name "OUT19_P") (class "Default")
      (node (ref "X-EAST") (pin "62") (pinfunction "62_62") (pintype "bidirectional"))
      (node (ref "X-SOUTH") (pin "63") (pinfunction "63_63") (pintype "bidirectional"))
    )
    (net (code "86") (name "OUT20_N") (class "Default")
      (node (ref "X-SOUTH") (pin "70") (pinfunction "70_70") (pintype "bidirectional"))
    )
    (net (code "87") (name "OUT20_P") (class "Default")
      (node (ref "X-SOUTH") (pin "68") (pinfunction "68_68") (pintype "bidirectional"))
    )
    (net (code "88") (name "OUT21_N") (class "Default")
      (node (ref "X-EAST") (pin "59") (pinfunction "59_59") (pintype "bidirectional"))
      (node (ref "X-SOUTH") (pin "64") (pinfunction "64_64") (pintype "bidirectional"))
    )
    (net (code "89") (name "OUT21_P") (class "Default")
      (node (ref "X-EAST") (pin "61") (pinfunction "61_61") (pintype "bidirectional"))
      (node (ref "X-SOUTH") (pin "62") (pinfunction "62_62") (pintype "bidirectional"))
    )
    (net (code "90") (name "OUT22_N") (class "Default")
      (node (ref "X-SOUTH") (pin "59") (pinfunction "59_59") (pintype "bidirectional"))
    )
    (net (code "91") (name "OUT22_P") (class "Default")
      (node (ref "X-SOUTH") (pin "57") (pinfunction "57_57") (pintype "bidirectional"))
    )
    (net (code "92") (name "OUT23_N") (class "Default")
      (node (ref "X-EAST") (pin "66") (pinfunction "66_66") (pintype "bidirectional"))
      (node (ref "X-SOUTH") (pin "53") (pinfunction "53_53") (pintype "bidirectional"))
    )
    (net (code "93") (name "OUT23_P") (class "Default")
      (node (ref "X-EAST") (pin "68") (pinfunction "68_68") (pintype "bidirectional"))
      (node (ref "X-SOUTH") (pin "51") (pinfunction "51_51") (pintype "bidirectional"))
    )
    (net (code "94") (name "OUT24_N") (class "Default")
      (node (ref "X-SOUTH") (pin "52") (pinfunction "52_52") (pintype "bidirectional"))
    )
    (net (code "95") (name "OUT24_P") (class "Default")
      (node (ref "X-SOUTH") (pin "50") (pinfunction "50_50") (pintype "bidirectional"))
    )
    (net (code "96") (name "OUT25_N") (class "Default")
      (node (ref "X-EAST") (pin "65") (pinfunction "65_65") (pintype "bidirectional"))
      (node (ref "X-SOUTH") (pin "58") (pinfunction "58_58") (pintype "bidirectional"))
    )
    (net (code "97") (name "OUT25_P") (class "Default")
      (node (ref "X-EAST") (pin "67") (pinfunction "67_67") (pintype "bidirectional"))
      (node (ref "X-SOUTH") (pin "56") (pinfunction "56_56") (pintype "bidirectional"))
    )
    (net (code "98") (name "OUT26_N") (class "Default")
      (node (ref "X-SOUTH") (pin "47") (pinfunction "47_47") (pintype "bidirectional"))
    )
    (net (code "99") (name "OUT26_P") (class "Default")
      (node (ref "X-SOUTH") (pin "45") (pinfunction "45_45") (pintype "bidirectional"))
    )
    (net (code "100") (name "OUT27_N") (class "Default")
      (node (ref "X-EAST") (pin "73") (pinfunction "73_73") (pintype "bidirectional"))
      (node (ref "X-SOUTH") (pin "40") (pinfunction "40_40") (pintype "bidirectional"))
    )
    (net (code "101") (name "OUT27_P") (class "Default")
      (node (ref "X-EAST") (pin "75") (pinfunction "75_75") (pintype "bidirectional"))
      (node (ref "X-SOUTH") (pin "38") (pinfunction "38_38") (pintype "bidirectional"))
    )
    (net (code "102") (name "OUT28_N") (class "Default")
      (node (ref "X-SOUTH") (pin "46") (pinfunction "46_46") (pintype "bidirectional"))
    )
    (net (code "103") (name "OUT28_P") (class "Default")
      (node (ref "X-SOUTH") (pin "44") (pinfunction "44_44") (pintype "bidirectional"))
    )
    (net (code "104") (name "OUT29_N") (class "Default")
      (node (ref "X-EAST") (pin "72") (pinfunction "72_72") (pintype "bidirectional"))
      (node (ref "X-SOUTH") (pin "41") (pinfunction "41_41") (pintype "bidirectional"))
    )
    (net (code "105") (name "OUT29_P") (class "Default")
      (node (ref "X-EAST") (pin "74") (pinfunction "74_74") (pintype "bidirectional"))
      (node (ref "X-SOUTH") (pin "39") (pinfunction "39_39") (pintype "bidirectional"))
    )
    (net (code "106") (name "OUT30_N") (class "Default")
      (node (ref "X-SOUTH") (pin "34") (pinfunction "34_34") (pintype "bidirectional"))
    )
    (net (code "107") (name "OUT30_P") (class "Default")
      (node (ref "X-SOUTH") (pin "32") (pinfunction "32_32") (pintype "bidirectional"))
    )
    (net (code "108") (name "OUT31_N") (class "Default")
      (node (ref "X-EAST") (pin "78") (pinfunction "78_78") (pintype "bidirectional"))
      (node (ref "X-SOUTH") (pin "35") (pinfunction "35_35") (pintype "bidirectional"))
    )
    (net (code "109") (name "OUT31_P") (class "Default")
      (node (ref "X-EAST") (pin "80") (pinfunction "80_80") (pintype "bidirectional"))
      (node (ref "X-SOUTH") (pin "33") (pinfunction "33_33") (pintype "bidirectional"))
    )
    (net (code "110") (name "OUT32_N") (class "Default")
      (node (ref "X-SOUTH") (pin "28") (pinfunction "28_28") (pintype "bidirectional"))
    )
    (net (code "111") (name "OUT32_P") (class "Default")
      (node (ref "X-SOUTH") (pin "26") (pinfunction "26_26") (pintype "bidirectional"))
    )
    (net (code "112") (name "OUT33_N") (class "Default")
      (node (ref "X-NORTH") (pin "20") (pinfunction "20_20") (pintype "bidirectional"))
      (node (ref "X-WEST") (pin "67") (pinfunction "67_67") (pintype "bidirectional"))
    )
    (net (code "113") (name "OUT33_P") (class "Default")
      (node (ref "X-NORTH") (pin "22") (pinfunction "22_22") (pintype "bidirectional"))
      (node (ref "X-WEST") (pin "65") (pinfunction "65_65") (pintype "bidirectional"))
    )
    (net (code "114") (name "OUT34_N") (class "Default")
      (node (ref "X-NORTH") (pin "27") (pinfunction "27_27") (pintype "bidirectional"))
    )
    (net (code "115") (name "OUT34_P") (class "Default")
      (node (ref "X-NORTH") (pin "29") (pinfunction "29_29") (pintype "bidirectional"))
    )
    (net (code "116") (name "OUT35_N") (class "Default")
      (node (ref "X-NORTH") (pin "26") (pinfunction "26_26") (pintype "bidirectional"))
      (node (ref "X-WEST") (pin "61") (pinfunction "61_61") (pintype "bidirectional"))
    )
    (net (code "117") (name "OUT35_P") (class "Default")
      (node (ref "X-NORTH") (pin "28") (pinfunction "28_28") (pintype "bidirectional"))
      (node (ref "X-WEST") (pin "59") (pinfunction "59_59") (pintype "bidirectional"))
    )
    (net (code "118") (name "OUT36_N") (class "Default")
      (node (ref "X-NORTH") (pin "33") (pinfunction "33_33") (pintype "bidirectional"))
    )
    (net (code "119") (name "OUT36_P") (class "Default")
      (node (ref "X-NORTH") (pin "35") (pinfunction "35_35") (pintype "bidirectional"))
    )
    (net (code "120") (name "OUT37_N") (class "Default")
      (node (ref "X-NORTH") (pin "32") (pinfunction "32_32") (pintype "bidirectional"))
      (node (ref "X-WEST") (pin "47") (pinfunction "47_47") (pintype "bidirectional"))
    )
    (net (code "121") (name "OUT37_P") (class "Default")
      (node (ref "X-NORTH") (pin "34") (pinfunction "34_34") (pintype "bidirectional"))
      (node (ref "X-WEST") (pin "45") (pinfunction "45_45") (pintype "bidirectional"))
    )
    (net (code "122") (name "OUT38_N") (class "Default")
      (node (ref "X-NORTH") (pin "38") (pinfunction "38_38") (pintype "bidirectional"))
    )
    (net (code "123") (name "OUT38_P") (class "Default")
      (node (ref "X-NORTH") (pin "40") (pinfunction "40_40") (pintype "bidirectional"))
    )
    (net (code "124") (name "OUT39_N") (class "Default")
      (node (ref "X-NORTH") (pin "39") (pinfunction "39_39") (pintype "bidirectional"))
      (node (ref "X-WEST") (pin "80") (pinfunction "80_80") (pintype "bidirectional"))
    )
    (net (code "125") (name "OUT39_P") (class "Default")
      (node (ref "X-NORTH") (pin "41") (pinfunction "41_41") (pintype "bidirectional"))
      (node (ref "X-WEST") (pin "78") (pinfunction "78_78") (pintype "bidirectional"))
    )
    (net (code "126") (name "OUT40_N") (class "Default")
      (node (ref "X-NORTH") (pin "44") (pinfunction "44_44") (pintype "bidirectional"))
    )
    (net (code "127") (name "OUT40_P") (class "Default")
      (node (ref "X-NORTH") (pin "46") (pinfunction "46_46") (pintype "bidirectional"))
    )
    (net (code "128") (name "OUT41_N") (class "Default")
      (node (ref "X-NORTH") (pin "45") (pinfunction "45_45") (pintype "bidirectional"))
      (node (ref "X-WEST") (pin "74") (pinfunction "74_74") (pintype "bidirectional"))
    )
    (net (code "129") (name "OUT41_P") (class "Default")
      (node (ref "X-NORTH") (pin "47") (pinfunction "47_47") (pintype "bidirectional"))
      (node (ref "X-WEST") (pin "72") (pinfunction "72_72") (pintype "bidirectional"))
    )
    (net (code "130") (name "OUT42_N") (class "Default")
      (node (ref "X-NORTH") (pin "50") (pinfunction "50_50") (pintype "bidirectional"))
    )
    (net (code "131") (name "OUT42_P") (class "Default")
      (node (ref "X-NORTH") (pin "52") (pinfunction "52_52") (pintype "bidirectional"))
    )
    (net (code "132") (name "OUT43_N") (class "Default")
      (node (ref "X-NORTH") (pin "51") (pinfunction "51_51") (pintype "bidirectional"))
      (node (ref "X-WEST") (pin "68") (pinfunction "68_68") (pintype "bidirectional"))
    )
    (net (code "133") (name "OUT43_P") (class "Default")
      (node (ref "X-NORTH") (pin "53") (pinfunction "53_53") (pintype "bidirectional"))
      (node (ref "X-WEST") (pin "66") (pinfunction "66_66") (pintype "bidirectional"))
    )
    (net (code "134") (name "OUT44_N") (class "Default")
      (node (ref "X-NORTH") (pin "56") (pinfunction "56_56") (pintype "bidirectional"))
    )
    (net (code "135") (name "OUT44_P") (class "Default")
      (node (ref "X-NORTH") (pin "58") (pinfunction "58_58") (pintype "bidirectional"))
    )
    (net (code "136") (name "OUT45_N") (class "Default")
      (node (ref "X-NORTH") (pin "57") (pinfunction "57_57") (pintype "bidirectional"))
      (node (ref "X-WEST") (pin "62") (pinfunction "62_62") (pintype "bidirectional"))
    )
    (net (code "137") (name "OUT45_P") (class "Default")
      (node (ref "X-NORTH") (pin "59") (pinfunction "59_59") (pintype "bidirectional"))
      (node (ref "X-WEST") (pin "60") (pinfunction "60_60") (pintype "bidirectional"))
    )
    (net (code "138") (name "OUT46_N") (class "Default")
      (node (ref "X-NORTH") (pin "62") (pinfunction "62_62") (pintype "bidirectional"))
    )
    (net (code "139") (name "OUT46_P") (class "Default")
      (node (ref "X-NORTH") (pin "64") (pinfunction "64_64") (pintype "bidirectional"))
    )
    (net (code "140") (name "OUT47_N") (class "Default")
      (node (ref "X-NORTH") (pin "63") (pinfunction "63_63") (pintype "bidirectional"))
      (node (ref "X-WEST") (pin "56") (pinfunction "56_56") (pintype "bidirectional"))
    )
    (net (code "141") (name "OUT47_P") (class "Default")
      (node (ref "X-NORTH") (pin "65") (pinfunction "65_65") (pintype "bidirectional"))
      (node (ref "X-WEST") (pin "54") (pinfunction "54_54") (pintype "bidirectional"))
    )
    (net (code "142") (name "OUT48_N") (class "Default")
      (node (ref "X-NORTH") (pin "68") (pinfunction "68_68") (pintype "bidirectional"))
    )
    (net (code "143") (name "OUT48_P") (class "Default")
      (node (ref "X-NORTH") (pin "70") (pinfunction "70_70") (pintype "bidirectional"))
    )
    (net (code "144") (name "OUT49_N") (class "Default")
      (node (ref "X-EAST") (pin "48") (pinfunction "48_48") (pintype "bidirectional"))
      (node (ref "X-NORTH") (pin "74") (pinfunction "74_74") (pintype "bidirectional"))
    )
    (net (code "145") (name "OUT49_P") (class "Default")
      (node (ref "X-EAST") (pin "46") (pinfunction "46_46") (pintype "bidirectional"))
      (node (ref "X-NORTH") (pin "76") (pinfunction "76_76") (pintype "bidirectional"))
    )
    (net (code "146") (name "OUT50_N") (class "Default")
      (node (ref "X-NORTH") (pin "69") (pinfunction "69_69") (pintype "bidirectional"))
    )
    (net (code "147") (name "OUT50_P") (class "Default")
      (node (ref "X-NORTH") (pin "71") (pinfunction "71_71") (pintype "bidirectional"))
    )
    (net (code "148") (name "OUT51_N") (class "Default")
      (node (ref "X-EAST") (pin "42") (pinfunction "42_42") (pintype "bidirectional"))
      (node (ref "X-NORTH") (pin "80") (pinfunction "80_80") (pintype "bidirectional"))
    )
    (net (code "149") (name "OUT51_P") (class "Default")
      (node (ref "X-EAST") (pin "40") (pinfunction "40_40") (pintype "bidirectional"))
      (node (ref "X-NORTH") (pin "82") (pinfunction "82_82") (pintype "bidirectional"))
    )
    (net (code "150") (name "OUT52_N") (class "Default")
      (node (ref "X-NORTH") (pin "75") (pinfunction "75_75") (pintype "bidirectional"))
    )
    (net (code "151") (name "OUT52_P") (class "Default")
      (node (ref "X-NORTH") (pin "77") (pinfunction "77_77") (pintype "bidirectional"))
    )
    (net (code "152") (name "OUT53_N") (class "Default")
      (node (ref "X-EAST") (pin "47") (pinfunction "47_47") (pintype "bidirectional"))
      (node (ref "X-NORTH") (pin "86") (pinfunction "86_86") (pintype "bidirectional"))
    )
    (net (code "153") (name "OUT53_P") (class "Default")
      (node (ref "X-EAST") (pin "45") (pinfunction "45_45") (pintype "bidirectional"))
      (node (ref "X-NORTH") (pin "88") (pinfunction "88_88") (pintype "bidirectional"))
    )
    (net (code "154") (name "OUT54_N") (class "Default")
      (node (ref "X-NORTH") (pin "81") (pinfunction "81_81") (pintype "bidirectional"))
    )
    (net (code "155") (name "OUT54_P") (class "Default")
      (node (ref "X-NORTH") (pin "83") (pinfunction "83_83") (pintype "bidirectional"))
    )
    (net (code "156") (name "OUT55_N") (class "Default")
      (node (ref "X-EAST") (pin "41") (pinfunction "41_41") (pintype "bidirectional"))
      (node (ref "X-NORTH") (pin "92") (pinfunction "92_92") (pintype "bidirectional"))
    )
    (net (code "157") (name "OUT55_P") (class "Default")
      (node (ref "X-EAST") (pin "39") (pinfunction "39_39") (pintype "bidirectional"))
      (node (ref "X-NORTH") (pin "94") (pinfunction "94_94") (pintype "bidirectional"))
    )
    (net (code "158") (name "OUT56_N") (class "Default")
      (node (ref "X-NORTH") (pin "87") (pinfunction "87_87") (pintype "bidirectional"))
    )
    (net (code "159") (name "OUT56_P") (class "Default")
      (node (ref "X-NORTH") (pin "89") (pinfunction "89_89") (pintype "bidirectional"))
    )
    (net (code "160") (name "OUT57_N") (class "Default")
      (node (ref "X-EAST") (pin "35") (pinfunction "35_35") (pintype "bidirectional"))
      (node (ref "X-NORTH") (pin "98") (pinfunction "98_98") (pintype "bidirectional"))
    )
    (net (code "161") (name "OUT57_P") (class "Default")
      (node (ref "X-EAST") (pin "33") (pinfunction "33_33") (pintype "bidirectional"))
      (node (ref "X-NORTH") (pin "100") (pinfunction "100_100") (pintype "bidirectional"))
    )
    (net (code "162") (name "OUT58_N") (class "Default")
      (node (ref "X-NORTH") (pin "93") (pinfunction "93_93") (pintype "bidirectional"))
    )
    (net (code "163") (name "OUT58_P") (class "Default")
      (node (ref "X-NORTH") (pin "95") (pinfunction "95_95") (pintype "bidirectional"))
    )
    (net (code "164") (name "OUT59_N") (class "Default")
      (node (ref "X-EAST") (pin "27") (pinfunction "27_27") (pintype "bidirectional"))
      (node (ref "X-NORTH") (pin "104") (pinfunction "104_104") (pintype "bidirectional"))
    )
    (net (code "165") (name "OUT59_P") (class "Default")
      (node (ref "X-EAST") (pin "25") (pinfunction "25_25") (pintype "bidirectional"))
      (node (ref "X-NORTH") (pin "106") (pinfunction "106_106") (pintype "bidirectional"))
    )
    (net (code "166") (name "OUT60_N") (class "Default")
      (node (ref "X-NORTH") (pin "110") (pinfunction "110_110") (pintype "bidirectional"))
    )
    (net (code "167") (name "OUT60_P") (class "Default")
      (node (ref "X-NORTH") (pin "112") (pinfunction "112_112") (pintype "bidirectional"))
    )
    (net (code "168") (name "OUT61_N") (class "Default")
      (node (ref "X-EAST") (pin "36") (pinfunction "36_36") (pintype "bidirectional"))
      (node (ref "X-NORTH") (pin "99") (pinfunction "99_99") (pintype "bidirectional"))
    )
    (net (code "169") (name "OUT61_P") (class "Default")
      (node (ref "X-EAST") (pin "34") (pinfunction "34_34") (pintype "bidirectional"))
      (node (ref "X-NORTH") (pin "101") (pinfunction "101_101") (pintype "bidirectional"))
    )
    (net (code "170") (name "OUT62_N") (class "Default")
      (node (ref "X-NORTH") (pin "116") (pinfunction "116_116") (pintype "bidirectional"))
    )
    (net (code "171") (name "OUT62_P") (class "Default")
      (node (ref "X-NORTH") (pin "118") (pinfunction "118_118") (pintype "bidirectional"))
    )
    (net (code "172") (name "OUT63_N") (class "Default")
      (node (ref "X-EAST") (pin "30") (pinfunction "30_30") (pintype "bidirectional"))
      (node (ref "X-NORTH") (pin "105") (pinfunction "105_105") (pintype "bidirectional"))
    )
    (net (code "173") (name "OUT63_P") (class "Default")
      (node (ref "X-EAST") (pin "28") (pinfunction "28_28") (pintype "bidirectional"))
      (node (ref "X-NORTH") (pin "107") (pinfunction "107_107") (pintype "bidirectional"))
    )
    (net (code "174") (name "OUT64_N") (class "Default")
      (node (ref "X-NORTH") (pin "111") (pinfunction "111_111") (pintype "bidirectional"))
    )
    (net (code "175") (name "OUT64_P") (class "Default")
      (node (ref "X-NORTH") (pin "113") (pinfunction "113_113") (pintype "bidirectional"))
    )
    (net (code "176") (name "OUTCLK_N") (class "Default")
      (node (ref "X-NORTH") (pin "15") (pinfunction "15_15") (pintype "bidirectional"))
      (node (ref "X-WEST") (pin "53") (pinfunction "53_53") (pintype "bidirectional"))
    )
    (net (code "177") (name "OUTCLK_P") (class "Default")
      (node (ref "X-NORTH") (pin "17") (pinfunction "17_17") (pintype "bidirectional"))
      (node (ref "X-WEST") (pin "55") (pinfunction "55_55") (pintype "bidirectional"))
    )
    (net (code "178") (name "OUTCTR_N") (class "Default")
      (node (ref "X-SOUTH") (pin "125") (pinfunction "125_125") (pintype "bidirectional"))
      (node (ref "X-WEST") (pin "22") (pinfunction "22_22") (pintype "bidirectional"))
    )
    (net (code "179") (name "OUTCTR_P") (class "Default")
      (node (ref "X-SOUTH") (pin "123") (pinfunction "123_123") (pintype "bidirectional"))
      (node (ref "X-WEST") (pin "24") (pinfunction "24_24") (pintype "bidirectional"))
    )
    (net (code "180") (name "RES1") (class "Default")
      (node (ref "X-WEST") (pin "79") (pinfunction "79_79") (pintype "bidirectional"))
    )
    (net (code "181") (name "RES2") (class "Default")
      (node (ref "X-WEST") (pin "81") (pinfunction "81_81") (pintype "bidirectional"))
    )
    (net (code "182") (name "RES3") (class "Default")
      (node (ref "X-WEST") (pin "83") (pinfunction "83_83") (pintype "bidirectional"))
    )
    (net (code "183") (name "RES4") (class "Default")
      (node (ref "X-EAST") (pin "79") (pinfunction "79_79") (pintype "bidirectional"))
    )
    (net (code "184") (name "RES5") (class "Default")
      (node (ref "X-EAST") (pin "81") (pinfunction "81_81") (pintype "bidirectional"))
    )
    (net (code "185") (name "RES6") (class "Default")
      (node (ref "X-EAST") (pin "83") (pinfunction "83_83") (pintype "bidirectional"))
    )
    (net (code "186") (name "S00_N") (class "Default")
      (node (ref "X-SOUTH") (pin "16") (pinfunction "16_16") (pintype "bidirectional"))
    )
    (net (code "187") (name "S00_P") (class "Default")
      (node (ref "X-SOUTH") (pin "14") (pinfunction "14_14") (pintype "bidirectional"))
    )
    (net (code "188") (name "S01_N") (class "Default")
      (node (ref "X-SOUTH") (pin "17") (pinfunction "17_17") (pintype "bidirectional"))
    )
    (net (code "189") (name "S01_P") (class "Default")
      (node (ref "X-SOUTH") (pin "15") (pinfunction "15_15") (pintype "bidirectional"))
    )
    (net (code "190") (name "S02_N") (class "Default")
      (node (ref "X-SOUTH") (pin "22") (pinfunction "22_22") (pintype "bidirectional"))
    )
    (net (code "191") (name "S02_P") (class "Default")
      (node (ref "X-SOUTH") (pin "20") (pinfunction "20_20") (pintype "bidirectional"))
    )
    (net (code "192") (name "S03_N") (class "Default")
      (node (ref "X-SOUTH") (pin "23") (pinfunction "23_23") (pintype "bidirectional"))
    )
    (net (code "193") (name "S03_P") (class "Default")
      (node (ref "X-SOUTH") (pin "21") (pinfunction "21_21") (pintype "bidirectional"))
    )
    (net (code "194") (name "S05_N") (class "Default")
      (node (ref "X-SOUTH") (pin "29") (pinfunction "29_29") (pintype "bidirectional"))
    )
    (net (code "195") (name "S05_P") (class "Default")
      (node (ref "X-SOUTH") (pin "27") (pinfunction "27_27") (pintype "bidirectional"))
    )
    (net (code "196") (name "S38_N") (class "Default")
      (node (ref "X-SOUTH") (pin "130") (pinfunction "130_130") (pintype "bidirectional"))
    )
    (net (code "197") (name "S38_P") (class "Default")
      (node (ref "X-SOUTH") (pin "128") (pinfunction "128_128") (pintype "bidirectional"))
    )
    (net (code "198") (name "S39_N") (class "Default")
      (node (ref "X-SOUTH") (pin "131") (pinfunction "131_131") (pintype "bidirectional"))
    )
    (net (code "199") (name "S39_P") (class "Default")
      (node (ref "X-SOUTH") (pin "129") (pinfunction "129_129") (pintype "bidirectional"))
    )
    (net (code "200") (name "SYS_RES_N") (class "Default")
      (node (ref "X-EAST") (pin "22") (pinfunction "22_22") (pintype "bidirectional"))
      (node (ref "X-NORTH") (pin "125") (pinfunction "125_125") (pintype "bidirectional"))
    )
    (net (code "201") (name "S_CHK_EN") (class "Default")
      (node (ref "X-EAST") (pin "94") (pinfunction "94_94") (pintype "bidirectional"))
      (node (ref "X-SOUTH") (pin "8") (pinfunction "8_8") (pintype "bidirectional"))
    )
    (net (code "202") (name "S_CHK_V") (class "Default")
      (node (ref "X-EAST") (pin "92") (pinfunction "92_92") (pintype "bidirectional"))
      (node (ref "X-SOUTH") (pin "10") (pinfunction "10_10") (pintype "bidirectional"))
    )
    (net (code "203") (name "S_I2C_EN") (class "Default")
      (node (ref "X-SOUTH") (pin "137") (pinfunction "137_137") (pintype "bidirectional"))
      (node (ref "X-WEST") (pin "7") (pinfunction "7_7") (pintype "bidirectional"))
    )
    (net (code "204") (name "S_I2C_V") (class "Default")
      (node (ref "X-SOUTH") (pin "135") (pinfunction "135_135") (pintype "bidirectional"))
      (node (ref "X-WEST") (pin "9") (pinfunction "9_9") (pintype "bidirectional"))
    )
    (net (code "205") (name "S_SCK") (class "Default")
      (node (ref "X-SOUTH") (pin "144") (pinfunction "144_144") (pintype "bidirectional"))
      (node (ref "X-WEST") (pin "2") (pinfunction "2_2") (pintype "bidirectional"))
    )
    (net (code "206") (name "S_SCL") (class "Default")
      (node (ref "X-SOUTH") (pin "143") (pinfunction "143_143") (pintype "bidirectional"))
      (node (ref "X-WEST") (pin "1") (pinfunction "1_1") (pintype "bidirectional"))
    )
    (net (code "207") (name "S_SDA") (class "Default")
      (node (ref "X-SOUTH") (pin "141") (pinfunction "141_141") (pintype "bidirectional"))
      (node (ref "X-WEST") (pin "3") (pinfunction "3_3") (pintype "bidirectional"))
    )
    (net (code "208") (name "S_SDI") (class "Default")
      (node (ref "X-SOUTH") (pin "140") (pinfunction "140_140") (pintype "bidirectional"))
      (node (ref "X-WEST") (pin "6") (pinfunction "6_6") (pintype "bidirectional"))
    )
    (net (code "209") (name "S_SDO") (class "Default")
      (node (ref "X-SOUTH") (pin "142") (pinfunction "142_142") (pintype "bidirectional"))
      (node (ref "X-WEST") (pin "4") (pinfunction "4_4") (pintype "bidirectional"))
    )
    (net (code "210") (name "S_SPI_EN") (class "Default")
      (node (ref "X-SOUTH") (pin "136") (pinfunction "136_136") (pintype "bidirectional"))
      (node (ref "X-WEST") (pin "8") (pinfunction "8_8") (pintype "bidirectional"))
    )
    (net (code "211") (name "S_SPI_V") (class "Default")
      (node (ref "X-SOUTH") (pin "134") (pinfunction "134_134") (pintype "bidirectional"))
      (node (ref "X-WEST") (pin "10") (pinfunction "10_10") (pintype "bidirectional"))
    )
    (net (code "212") (name "S_VE") (class "Default")
      (node (ref "C7") (pin "1") (pinfunction "1_1") (pintype "passive"))
      (node (ref "SE") (pin "1") (pinfunction "1_1") (pintype "passive"))
      (node (ref "X-SOUTH") (pin "13") (pinfunction "13_13") (pintype "bidirectional"))
      (node (ref "X-SOUTH") (pin "19") (pinfunction "19_19") (pintype "bidirectional"))
      (node (ref "X-SOUTH") (pin "31") (pinfunction "31_31") (pintype "bidirectional"))
      (node (ref "X-SOUTH") (pin "37") (pinfunction "37_37") (pintype "bidirectional"))
    )
    (net (code "213") (name "S_VE_CV") (class "Default")
      (node (ref "X-EAST") (pin "100") (pinfunction "100_100") (pintype "bidirectional"))
      (node (ref "X-SOUTH") (pin "2") (pinfunction "2_2") (pintype "bidirectional"))
    )
    (net (code "214") (name "S_VE_OV") (class "Default")
      (node (ref "X-EAST") (pin "99") (pinfunction "99_99") (pintype "bidirectional"))
      (node (ref "X-SOUTH") (pin "1") (pinfunction "1_1") (pintype "bidirectional"))
    )
    (net (code "215") (name "S_VE_RS") (class "Default")
      (node (ref "X-EAST") (pin "84") (pinfunction "84_84") (pintype "bidirectional"))
      (node (ref "X-SOUTH") (pin "25") (pinfunction "25_25") (pintype "bidirectional"))
    )
    (net (code "216") (name "S_VE_UV") (class "Default")
      (node (ref "X-EAST") (pin "89") (pinfunction "89_89") (pintype "bidirectional"))
      (node (ref "X-SOUTH") (pin "7") (pinfunction "7_7") (pintype "bidirectional"))
    )
    (net (code "217") (name "S_VS") (class "Default")
      (node (ref "C6") (pin "1") (pinfunction "1_1") (pintype "passive"))
      (node (ref "SW") (pin "1") (pinfunction "1_1") (pintype "passive"))
      (node (ref "X-SOUTH") (pin "49") (pinfunction "49_49") (pintype "bidirectional"))
      (node (ref "X-SOUTH") (pin "55") (pinfunction "55_55") (pintype "bidirectional"))
      (node (ref "X-SOUTH") (pin "61") (pinfunction "61_61") (pintype "bidirectional"))
      (node (ref "X-SOUTH") (pin "67") (pinfunction "67_67") (pintype "bidirectional"))
      (node (ref "X-SOUTH") (pin "79") (pinfunction "79_79") (pintype "bidirectional"))
      (node (ref "X-SOUTH") (pin "85") (pinfunction "85_85") (pintype "bidirectional"))
      (node (ref "X-SOUTH") (pin "91") (pinfunction "91_91") (pintype "bidirectional"))
      (node (ref "X-SOUTH") (pin "97") (pinfunction "97_97") (pintype "bidirectional"))
    )
    (net (code "218") (name "S_VS_CV") (class "Default")
      (node (ref "X-EAST") (pin "98") (pinfunction "98_98") (pintype "bidirectional"))
      (node (ref "X-SOUTH") (pin "4") (pinfunction "4_4") (pintype "bidirectional"))
    )
    (net (code "219") (name "S_VS_OV") (class "Default")
      (node (ref "X-EAST") (pin "97") (pinfunction "97_97") (pintype "bidirectional"))
      (node (ref "X-SOUTH") (pin "3") (pinfunction "3_3") (pintype "bidirectional"))
    )
    (net (code "220") (name "S_VS_RS") (class "Default")
      (node (ref "X-EAST") (pin "86") (pinfunction "86_86") (pintype "bidirectional"))
      (node (ref "X-SOUTH") (pin "73") (pinfunction "73_73") (pintype "bidirectional"))
    )
    (net (code "221") (name "S_VS_UV") (class "Default")
      (node (ref "X-EAST") (pin "87") (pinfunction "87_87") (pintype "bidirectional"))
      (node (ref "X-SOUTH") (pin "9") (pinfunction "9_9") (pintype "bidirectional"))
    )
    (net (code "222") (name "S_VW") (class "Default")
      (node (ref "C2") (pin "1") (pinfunction "1_1") (pintype "passive"))
      (node (ref "SW") (pin "2") (pinfunction "2_2") (pintype "passive"))
      (node (ref "X-SOUTH") (pin "109") (pinfunction "109_109") (pintype "bidirectional"))
      (node (ref "X-SOUTH") (pin "115") (pinfunction "115_115") (pintype "bidirectional"))
      (node (ref "X-SOUTH") (pin "127") (pinfunction "127_127") (pintype "bidirectional"))
      (node (ref "X-SOUTH") (pin "133") (pinfunction "133_133") (pintype "bidirectional"))
    )
    (net (code "223") (name "S_VW_CV") (class "Default")
      (node (ref "X-EAST") (pin "96") (pinfunction "96_96") (pintype "bidirectional"))
      (node (ref "X-SOUTH") (pin "6") (pinfunction "6_6") (pintype "bidirectional"))
    )
    (net (code "224") (name "S_VW_OV") (class "Default")
      (node (ref "X-EAST") (pin "95") (pinfunction "95_95") (pintype "bidirectional"))
      (node (ref "X-SOUTH") (pin "5") (pinfunction "5_5") (pintype "bidirectional"))
    )
    (net (code "225") (name "S_VW_RS") (class "Default")
      (node (ref "X-EAST") (pin "88") (pinfunction "88_88") (pintype "bidirectional"))
      (node (ref "X-SOUTH") (pin "121") (pinfunction "121_121") (pintype "bidirectional"))
    )
    (net (code "226") (name "S_VW_UV") (class "Default")
      (node (ref "X-EAST") (pin "85") (pinfunction "85_85") (pintype "bidirectional"))
      (node (ref "X-SOUTH") (pin "11") (pinfunction "11_11") (pintype "bidirectional"))
    )
    (net (code "227") (name "TCK") (class "Default")
      (node (ref "X-WEST") (pin "12") (pinfunction "12_12") (pintype "bidirectional"))
    )
    (net (code "228") (name "TDI") (class "Default")
      (node (ref "X-WEST") (pin "16") (pinfunction "16_16") (pintype "bidirectional"))
    )
    (net (code "229") (name "TDIG1") (class "Default")
      (node (ref "X-EAST") (pin "18") (pinfunction "18_18") (pintype "bidirectional"))
      (node (ref "X-NORTH") (pin "123") (pinfunction "123_123") (pintype "bidirectional"))
    )
    (net (code "230") (name "TDIG2") (class "Default")
      (node (ref "X-NORTH") (pin "130") (pinfunction "130_130") (pintype "bidirectional"))
    )
    (net (code "231") (name "TDO") (class "Default")
      (node (ref "X-WEST") (pin "18") (pinfunction "18_18") (pintype "bidirectional"))
    )
    (net (code "232") (name "TMS") (class "Default")
      (node (ref "X-WEST") (pin "14") (pinfunction "14_14") (pintype "bidirectional"))
    )
    (net (code "233") (name "TP9") (class "Default")
      (node (ref "X-NORTH") (pin "119") (pinfunction "119_119") (pintype "bidirectional"))
    )
    (net (code "234") (name "T_EXP1") (class "Default")
      (node (ref "X-EAST") (pin "12") (pinfunction "12_12") (pintype "bidirectional"))
      (node (ref "X-NORTH") (pin "131") (pinfunction "131_131") (pintype "bidirectional"))
    )
    (net (code "235") (name "T_EXP2") (class "Default")
      (node (ref "X-EAST") (pin "16") (pinfunction "16_16") (pintype "bidirectional"))
      (node (ref "X-NORTH") (pin "117") (pinfunction "117_117") (pintype "bidirectional"))
    )
    (net (code "236") (name "W_EN") (class "Default")
      (node (ref "X-WEST") (pin "19") (pinfunction "19_19") (pintype "bidirectional"))
    )
    (net (code "237") (name "W_I2C_EN") (class "Default")
      (node (ref "X-WEST") (pin "13") (pinfunction "13_13") (pintype "bidirectional"))
    )
    (net (code "238") (name "W_I2C_V") (class "Default")
      (node (ref "X-WEST") (pin "11") (pinfunction "11_11") (pintype "bidirectional"))
    )
    (net (code "239") (name "W_SCL") (class "Default")
      (node (ref "X-WEST") (pin "15") (pinfunction "15_15") (pintype "bidirectional"))
    )
    (net (code "240") (name "W_SDA") (class "Default")
      (node (ref "X-WEST") (pin "17") (pinfunction "17_17") (pintype "bidirectional"))
    )
    (net (code "241") (name "W_VW") (class "Default")
      (node (ref "C8") (pin "1") (pinfunction "1_1") (pintype "passive"))
      (node (ref "NW") (pin "2") (pinfunction "2_2") (pintype "passive"))
    )
    (net (code "242") (name "W_VW_CV") (class "Default")
      (node (ref "X-WEST") (pin "90") (pinfunction "90_90") (pintype "bidirectional"))
    )
    (net (code "243") (name "W_VW_OV") (class "Default")
      (node (ref "X-WEST") (pin "93") (pinfunction "93_93") (pintype "bidirectional"))
    )
    (net (code "244") (name "W_VW_UV") (class "Default")
      (node (ref "X-WEST") (pin "91") (pinfunction "91_91") (pintype "bidirectional"))
    )
    (net (code "245") (name "unconnected-(X-EAST-PadM1)") (class "Default")
      (node (ref "X-EAST") (pin "M1") (pinfunction "M1_M1") (pintype "bidirectional"))
    )
    (net (code "246") (name "unconnected-(X-EAST-PadM2)") (class "Default")
      (node (ref "X-EAST") (pin "M2") (pinfunction "M2_M2") (pintype "bidirectional"))
    )
    (net (code "247") (name "unconnected-(X-NORTH-PadM1)") (class "Default")
      (node (ref "X-NORTH") (pin "M1") (pinfunction "M1_M1") (pintype "bidirectional"))
    )
    (net (code "248") (name "unconnected-(X-NORTH-PadM2)") (class "Default")
      (node (ref "X-NORTH") (pin "M2") (pinfunction "M2_M2") (pintype "bidirectional"))
    )
    (net (code "249") (name "unconnected-(X-SOUTH-PadM1)") (class "Default")
      (node (ref "X-SOUTH") (pin "M1") (pinfunction "M1_M1") (pintype "bidirectional"))
    )
    (net (code "250") (name "unconnected-(X-SOUTH-PadM2)") (class "Default")
      (node (ref "X-SOUTH") (pin "M2") (pinfunction "M2_M2") (pintype "bidirectional"))
    )
    (net (code "251") (name "unconnected-(X-WEST-PadM1)") (class "Default")
      (node (ref "X-WEST") (pin "M1") (pinfunction "M1_M1") (pintype "bidirectional"))
    )
    (net (code "252") (name "unconnected-(X-WEST-PadM2)") (class "Default")
      (node (ref "X-WEST") (pin "M2") (pinfunction "M2_M2") (pintype "bidirectional"))
    )
  )
)
